# 2nd_project.net
KiCad netlist of a schematic drawn in EAGLE
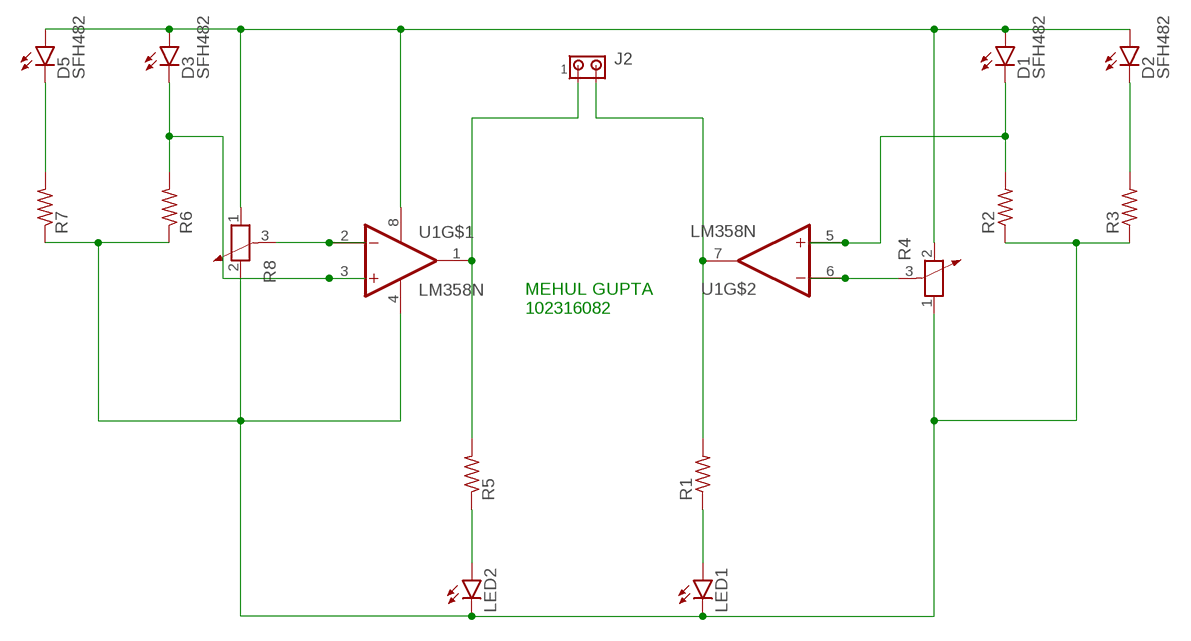
[diagram p0: schematic, sheet 1]

(export (version "E")
  (design (tool "Eeschema 10.0.6"))
  (components
    (comp (ref "D1")
      (value "SFH482")
      (footprint "eagle-import:SFH482")
      (libsource (lib "eagle-import") (part "SFH482"))
    )
    (comp (ref "D2")
      (value "SFH482")
      (footprint "eagle-import:SFH482")
      (libsource (lib "eagle-import") (part "SFH482"))
    )
    (comp (ref "D3")
      (value "SFH482")
      (footprint "eagle-import:SFH482")
      (libsource (lib "eagle-import") (part "SFH482"))
    )
    (comp (ref "D5")
      (value "SFH482")
      (footprint "eagle-import:SFH482")
      (libsource (lib "eagle-import") (part "SFH482"))
    )
    (comp (ref "J2")
      (value "MTA02-100")
      (footprint "eagle-import:10X02MTA")
      (libsource (lib "eagle-import") (part "MTA02-100"))
    )
    (comp (ref "LED1")
      (value "LED3MM")
      (footprint "eagle-import:LED3MM")
      (libsource (lib "eagle-import") (part "LED3MM"))
    )
    (comp (ref "LED2")
      (value "LED3MM")
      (footprint "eagle-import:LED3MM")
      (libsource (lib "eagle-import") (part "LED3MM"))
    )
    (comp (ref "R1")
      (value "R-US_0204/5")
      (footprint "eagle-import:0204_5")
      (libsource (lib "eagle-import") (part "R-US_0204/5"))
    )
    (comp (ref "R2")
      (value "R-US_0204/5")
      (footprint "eagle-import:0204_5")
      (libsource (lib "eagle-import") (part "R-US_0204/5"))
    )
    (comp (ref "R3")
      (value "R-US_0204/5")
      (footprint "eagle-import:0204_5")
      (libsource (lib "eagle-import") (part "R-US_0204/5"))
    )
    (comp (ref "R4")
      (value "POTENTIOMETER_PT-10")
      (footprint "eagle-import:PT-10")
      (libsource (lib "eagle-import") (part "POTENTIOMETER_PT-10"))
    )
    (comp (ref "R5")
      (value "R-US_0204/5")
      (footprint "eagle-import:0204_5")
      (libsource (lib "eagle-import") (part "R-US_0204/5"))
    )
    (comp (ref "R6")
      (value "R-US_0204/5")
      (footprint "eagle-import:0204_5")
      (libsource (lib "eagle-import") (part "R-US_0204/5"))
    )
    (comp (ref "R7")
      (value "R-US_0204/5")
      (footprint "eagle-import:0204_5")
      (libsource (lib "eagle-import") (part "R-US_0204/5"))
    )
    (comp (ref "R8")
      (value "POTENTIOMETER_PT-10")
      (footprint "eagle-import:PT-10")
      (libsource (lib "eagle-import") (part "POTENTIOMETER_PT-10"))
    )
    (comp (ref "U1")
      (value "LM358N")
      (footprint "eagle-import:DIP762W46P254L960H508Q8")
      (fields (field (name "MF") "Harris Corporation"))
      (libsource (lib "eagle-import") (part "LM358N"))
    )
  )
  (nets
    (net (code "1") (name "Net-(D1-C)") (class "Default")
      (node (ref "D1") (pin "K") (pinfunction "C_K") (pintype "passive"))
      (node (ref "R2") (pin "2") (pinfunction "2_2") (pintype "passive"))
      (node (ref "U1") (pin "5") (pinfunction "2IN+_5") (pintype "input"))
    )
    (net (code "2") (name "Net-(D2-C)") (class "Default")
      (node (ref "D2") (pin "K") (pinfunction "C_K") (pintype "passive"))
      (node (ref "R3") (pin "2") (pinfunction "2_2") (pintype "passive"))
    )
    (net (code "3") (name "Net-(D3-C)") (class "Default")
      (node (ref "D3") (pin "K") (pinfunction "C_K") (pintype "passive"))
      (node (ref "R6") (pin "2") (pinfunction "2_2") (pintype "passive"))
      (node (ref "U1") (pin "3") (pinfunction "1IN+_3") (pintype "input"))
    )
    (net (code "4") (name "Net-(D5-C)") (class "Default")
      (node (ref "D5") (pin "K") (pinfunction "C_K") (pintype "passive"))
      (node (ref "R7") (pin "2") (pinfunction "2_2") (pintype "passive"))
    )
    (net (code "5") (name "Net-(LED1-C)") (class "Default")
      (node (ref "LED1") (pin "K") (pinfunction "C_K") (pintype "passive"))
      (node (ref "LED2") (pin "K") (pinfunction "C_K") (pintype "passive"))
      (node (ref "R2") (pin "1") (pinfunction "1_1") (pintype "passive"))
      (node (ref "R3") (pin "1") (pinfunction "1_1") (pintype "passive"))
      (node (ref "R4") (pin "1") (pinfunction "1_1") (pintype "passive"))
      (node (ref "R6") (pin "1") (pinfunction "1_1") (pintype "passive"))
      (node (ref "R7") (pin "1") (pinfunction "1_1") (pintype "passive"))
      (node (ref "R8") (pin "2") (pinfunction "2_2") (pintype "passive"))
      (node (ref "U1") (pin "4") (pinfunction "GND_4") (pintype "power_in"))
    )
    (net (code "6") (name "Net-(LED1-PadA)") (class "Default")
      (node (ref "LED1") (pin "A") (pinfunction "A_A") (pintype "passive"))
      (node (ref "R1") (pin "1") (pinfunction "1_1") (pintype "passive"))
    )
    (net (code "7") (name "Net-(LED2-PadA)") (class "Default")
      (node (ref "LED2") (pin "A") (pinfunction "A_A") (pintype "passive"))
      (node (ref "R5") (pin "1") (pinfunction "1_1") (pintype "passive"))
    )
    (net (code "8") (name "Net-(U1A-1IN-)") (class "Default")
      (node (ref "R8") (pin "3") (pinfunction "3_3") (pintype "passive"))
      (node (ref "U1") (pin "2") (pinfunction "1IN-_2") (pintype "input"))
    )
    (net (code "9") (name "Net-(U1A-1OUT)") (class "Default")
      (node (ref "J2") (pin "1") (pinfunction "1_1") (pintype "passive"))
      (node (ref "R5") (pin "2") (pinfunction "2_2") (pintype "passive"))
      (node (ref "U1") (pin "1") (pinfunction "1OUT_1") (pintype "output"))
    )
    (net (code "10") (name "Net-(U1A-VCC)") (class "Default")
      (node (ref "D1") (pin "A") (pinfunction "A_A") (pintype "passive"))
      (node (ref "D2") (pin "A") (pinfunction "A_A") (pintype "passive"))
      (node (ref "D3") (pin "A") (pinfunction "A_A") (pintype "passive"))
      (node (ref "D5") (pin "A") (pinfunction "A_A") (pintype "passive"))
      (node (ref "R4") (pin "2") (pinfunction "2_2") (pintype "passive"))
      (node (ref "R8") (pin "1") (pinfunction "1_1") (pintype "passive"))
      (node (ref "U1") (pin "8") (pinfunction "VCC_8") (pintype "power_in"))
    )
    (net (code "11") (name "Net-(U1B-2IN-)") (class "Default")
      (node (ref "R4") (pin "3") (pinfunction "3_3") (pintype "passive"))
      (node (ref "U1") (pin "6") (pinfunction "2IN-_6") (pintype "input"))
    )
    (net (code "12") (name "Net-(U1B-2OUT)") (class "Default")
      (node (ref "J2") (pin "2") (pinfunction "2_2") (pintype "passive"))
      (node (ref "R1") (pin "2") (pinfunction "2_2") (pintype "passive"))
      (node (ref "U1") (pin "7") (pinfunction "2OUT_7") (pintype "output"))
    )
  )
)
